# sensor_tag.net
KiCad netlist of a schematic drawn in EAGLE
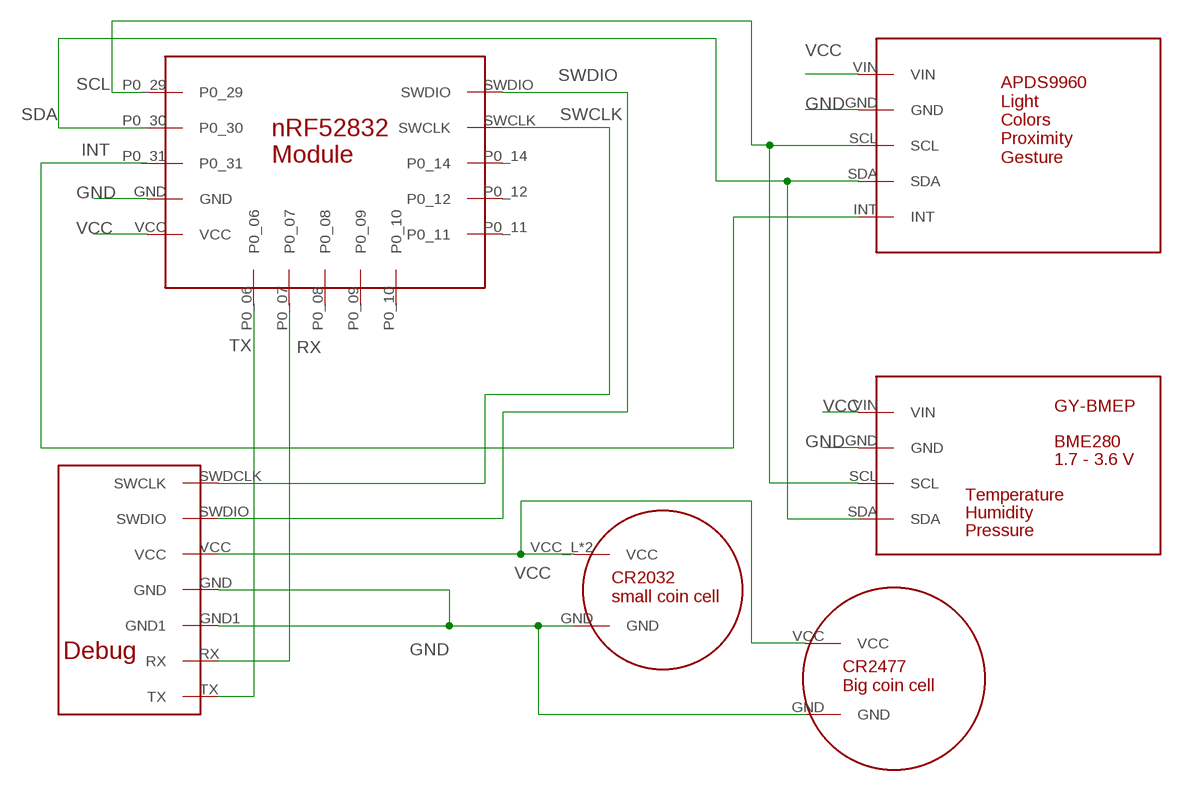
[diagram p0: schematic, sheet 1]

(export (version "E")
  (design (tool "Eeschema 10.0.6"))
  (components
    (comp (ref "U$1")
      (value "GY-BMEPGY-BMEP-NOHOLE")
      (footprint "eagle-import:GY-BMEP-NOHOLE")
      (libsource (lib "eagle-import") (part "GY-BMEPGY-BMEP-NOHOLE"))
    )
    (comp (ref "U$2")
      (value "APDS9960_MODULEAPDS9960-FULL")
      (footprint "eagle-import:APDS9960-FULL")
      (libsource (lib "eagle-import") (part "APDS9960_MODULEAPDS9960-FULL"))
    )
    (comp (ref "U$3")
      (value "NRF52832_MODULENRF52832_MOD_SMALL")
      (footprint "eagle-import:NRF52832_MOD_SMALL")
      (libsource (lib "eagle-import") (part "NRF52832_MODULENRF52832_MOD_SMALL"))
    )
    (comp (ref "U$4")
      (value "CR2032")
      (footprint "eagle-import:CR2032_SMD")
      (libsource (lib "eagle-import") (part "CR2032"))
    )
    (comp (ref "U$5")
      (value "NRF_TAG_DEBUG")
      (footprint "eagle-import:NRF_TAG_DEBUG")
      (libsource (lib "eagle-import") (part "NRF_TAG_DEBUG"))
    )
    (comp (ref "U$6")
      (value "CR2477")
      (footprint "eagle-import:CR2477")
      (libsource (lib "eagle-import") (part "CR2477"))
    )
  )
  (nets
    (net (code "1") (name "/GND") (class "Default")
      (node (ref "U$1") (pin "GND") (pinfunction "GND_GND") (pintype "bidirectional"))
      (node (ref "U$2") (pin "GND") (pinfunction "GND_GND") (pintype "bidirectional"))
      (node (ref "U$3") (pin "GND") (pinfunction "GND_GND") (pintype "bidirectional"))
      (node (ref "U$4") (pin "GND") (pinfunction "GND_GND") (pintype "bidirectional"))
      (node (ref "U$5") (pin "GND") (pinfunction "GND_GND") (pintype "bidirectional"))
      (node (ref "U$5") (pin "GND1") (pinfunction "GND1_GND1") (pintype "bidirectional"))
      (node (ref "U$6") (pin "GND") (pinfunction "GND_GND") (pintype "bidirectional"))
    )
    (net (code "2") (name "/INT") (class "Default")
      (node (ref "U$2") (pin "INT") (pinfunction "INT_INT") (pintype "bidirectional"))
      (node (ref "U$3") (pin "P0_31") (pinfunction "P0_31_P0_31") (pintype "bidirectional"))
    )
    (net (code "3") (name "/RX") (class "Default")
      (node (ref "U$3") (pin "P0_07") (pinfunction "P0_07_P0_07") (pintype "bidirectional"))
      (node (ref "U$5") (pin "RX") (pinfunction "RX_RX") (pintype "bidirectional"))
    )
    (net (code "4") (name "/SCL") (class "Default")
      (node (ref "U$1") (pin "SCL") (pinfunction "SCL_SCL") (pintype "bidirectional"))
      (node (ref "U$2") (pin "SCL") (pinfunction "SCL_SCL") (pintype "bidirectional"))
      (node (ref "U$3") (pin "P0_29") (pinfunction "P0_29_P0_29") (pintype "bidirectional"))
    )
    (net (code "5") (name "/SDA") (class "Default")
      (node (ref "U$1") (pin "SDA") (pinfunction "SDA_SDA") (pintype "bidirectional"))
      (node (ref "U$2") (pin "SDA") (pinfunction "SDA_SDA") (pintype "bidirectional"))
      (node (ref "U$3") (pin "P0_30") (pinfunction "P0_30_P0_30") (pintype "bidirectional"))
    )
    (net (code "6") (name "/SWCLK") (class "Default")
      (node (ref "U$3") (pin "SWCLK") (pinfunction "SWCLK_SWCLK") (pintype "bidirectional"))
      (node (ref "U$5") (pin "SWDCLK") (pinfunction "SWCLK_SWDCLK") (pintype "bidirectional"))
    )
    (net (code "7") (name "/SWDIO") (class "Default")
      (node (ref "U$3") (pin "SWDIO") (pinfunction "SWDIO_SWDIO") (pintype "bidirectional"))
      (node (ref "U$5") (pin "SWDIO") (pinfunction "SWDIO_SWDIO") (pintype "bidirectional"))
    )
    (net (code "8") (name "/TX") (class "Default")
      (node (ref "U$3") (pin "P0_06") (pinfunction "P0_06_P0_06") (pintype "bidirectional"))
      (node (ref "U$5") (pin "TX") (pinfunction "TX_TX") (pintype "bidirectional"))
    )
    (net (code "9") (name "/VCC") (class "Default")
      (node (ref "U$1") (pin "VIN") (pinfunction "VIN_VIN") (pintype "bidirectional"))
      (node (ref "U$2") (pin "VIN") (pinfunction "VIN_VIN") (pintype "bidirectional"))
      (node (ref "U$3") (pin "VCC") (pinfunction "VCC_VCC") (pintype "bidirectional"))
      (node (ref "U$4") (pin "VCC_L") (pinfunction "VCC_VCC_L") (pintype "bidirectional"))
      (node (ref "U$4") (pin "VCC_R") (pinfunction "VCC_VCC_R") (pintype "bidirectional"))
      (node (ref "U$5") (pin "VCC") (pinfunction "VCC_VCC") (pintype "bidirectional"))
      (node (ref "U$6") (pin "VCC") (pinfunction "VCC_VCC") (pintype "bidirectional"))
    )
    (net (code "10") (name "unconnected-(U$3-PadP0_08)") (class "Default")
      (node (ref "U$3") (pin "P0_08") (pinfunction "P0_08_P0_08") (pintype "bidirectional"))
    )
    (net (code "11") (name "unconnected-(U$3-PadP0_09)") (class "Default")
      (node (ref "U$3") (pin "P0_09") (pinfunction "P0_09_P0_09") (pintype "bidirectional"))
    )
    (net (code "12") (name "unconnected-(U$3-PadP0_10)") (class "Default")
      (node (ref "U$3") (pin "P0_10") (pinfunction "P0_10_P0_10") (pintype "bidirectional"))
    )
    (net (code "13") (name "unconnected-(U$3-PadP0_11)") (class "Default")
      (node (ref "U$3") (pin "P0_11") (pinfunction "P0_11_P0_11") (pintype "bidirectional"))
    )
    (net (code "14") (name "unconnected-(U$3-PadP0_12)") (class "Default")
      (node (ref "U$3") (pin "P0_12") (pinfunction "P0_12_P0_12") (pintype "bidirectional"))
    )
    (net (code "15") (name "unconnected-(U$3-PadP0_14)") (class "Default")
      (node (ref "U$3") (pin "P0_14") (pinfunction "P0_14_P0_14") (pintype "bidirectional"))
    )
  )
)
